# Sh_Input.net
KiCad netlist of a schematic drawn in Altium Designer
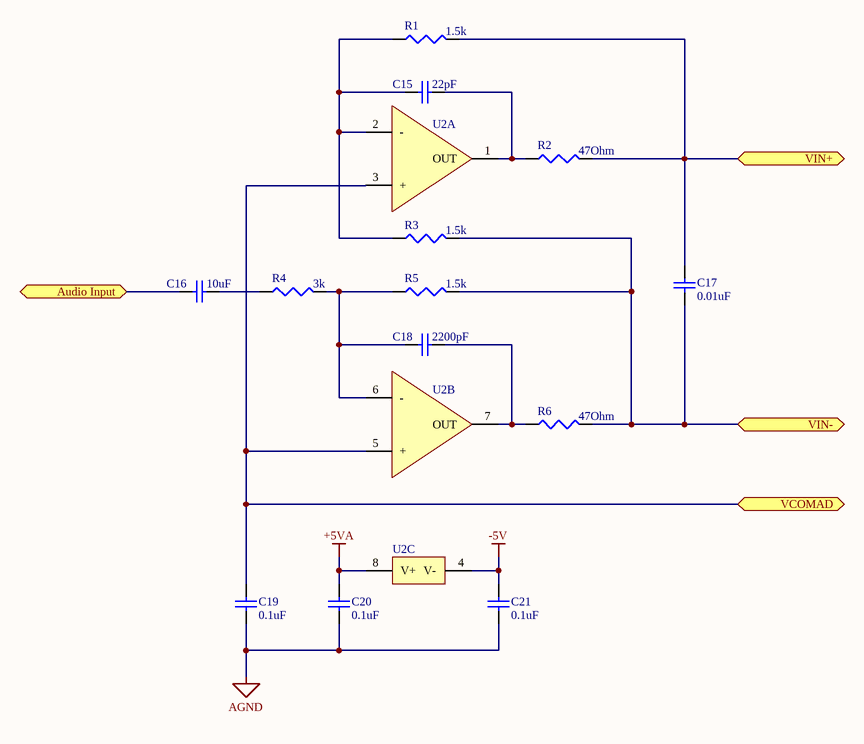
[diagram p0: Sh_Input.SchDoc]

(export (version "E")
  (design (tool "Eeschema 10.0.6"))
  (components
    (comp (ref "C15")
      (value "22pF")
      (footprint "1608[0603]")
      (description "Capacitor (Semiconductor SIM Model)")
      (fields (field (name "Comment") "Cap Semi") (field (name "PUBLISHER") "Altium Limited"))
      (libsource (lib "Miscellaneous Devices") (part "Cap Semi"))
    )
    (comp (ref "C16")
      (value "10uF")
      (footprint "1608[0603]")
      (description "Capacitor (Semiconductor SIM Model)")
      (fields (field (name "Comment") "Cap Semi") (field (name "PUBLISHER") "Altium Limited"))
      (libsource (lib "Miscellaneous Devices") (part "Cap Semi"))
    )
    (comp (ref "C17")
      (value "0.01uF")
      (footprint "1608[0603]")
      (description "Capacitor (Semiconductor SIM Model)")
      (fields (field (name "Comment") "Cap Semi") (field (name "PUBLISHER") "Altium Limited"))
      (libsource (lib "Miscellaneous Devices") (part "Cap Semi"))
    )
    (comp (ref "C18")
      (value "2200pF")
      (footprint "1608[0603]")
      (description "Capacitor (Semiconductor SIM Model)")
      (fields (field (name "Comment") "Cap Semi") (field (name "PUBLISHER") "Altium Limited"))
      (libsource (lib "Miscellaneous Devices") (part "Cap Semi"))
    )
    (comp (ref "C19")
      (value "0.1uF")
      (footprint "1608[0603]")
      (description "Capacitor (Semiconductor SIM Model)")
      (fields (field (name "Comment") "Cap Semi") (field (name "PUBLISHER") "Altium Limited"))
      (libsource (lib "Miscellaneous Devices") (part "Cap Semi"))
    )
    (comp (ref "C20")
      (value "0.1uF")
      (footprint "1608[0603]")
      (description "Capacitor (Semiconductor SIM Model)")
      (fields (field (name "Comment") "Cap Semi") (field (name "PUBLISHER") "Altium Limited"))
      (libsource (lib "Miscellaneous Devices") (part "Cap Semi"))
    )
    (comp (ref "C21")
      (value "0.1uF")
      (footprint "1608[0603]")
      (description "Capacitor (Semiconductor SIM Model)")
      (fields (field (name "Comment") "Cap Semi") (field (name "PUBLISHER") "Altium Limited"))
      (libsource (lib "Miscellaneous Devices") (part "Cap Semi"))
    )
    (comp (ref "R1")
      (value "1.5k")
      (footprint "J1-0603")
      (description "Resistor")
      (fields (field (name "Comment") "Res3") (field (name "PUBLISHER") "Altium Limited"))
      (libsource (lib "Miscellaneous Devices") (part "Res3"))
    )
    (comp (ref "R2")
      (value "47Ohm")
      (footprint "J1-0603")
      (description "Resistor")
      (fields (field (name "Comment") "Res3") (field (name "PUBLISHER") "Altium Limited"))
      (libsource (lib "Miscellaneous Devices") (part "Res3"))
    )
    (comp (ref "R3")
      (value "1.5k")
      (footprint "J1-0603")
      (description "Resistor")
      (fields (field (name "Comment") "Res3") (field (name "PUBLISHER") "Altium Limited"))
      (libsource (lib "Miscellaneous Devices") (part "Res3"))
    )
    (comp (ref "R4")
      (value "3k")
      (footprint "J1-0603")
      (description "Resistor")
      (fields (field (name "Comment") "Res3") (field (name "PUBLISHER") "Altium Limited"))
      (libsource (lib "Miscellaneous Devices") (part "Res3"))
    )
    (comp (ref "R5")
      (value "1.5k")
      (footprint "J1-0603")
      (description "Resistor")
      (fields (field (name "Comment") "Res3") (field (name "PUBLISHER") "Altium Limited"))
      (libsource (lib "Miscellaneous Devices") (part "Res3"))
    )
    (comp (ref "R6")
      (value "47Ohm")
      (footprint "J1-0603")
      (description "Resistor")
      (fields (field (name "Comment") "Res3") (field (name "PUBLISHER") "Altium Limited"))
      (libsource (lib "Miscellaneous Devices") (part "Res3"))
    )
    (comp (ref "U2")
      (value "NE5532A")
      (footprint "SOIC127P600-8AL")
      (description "Amplificateur Opérationnel")
      (libsource (lib "Bonjour") (part "Ampli_op"))
    )
  )
  (nets
    (net (code "1") (name "+5VA") (class "Default")
      (node (ref "C20") (pin "1") (pinfunction "1_1") (pintype "passive"))
      (node (ref "U2") (pin "8") (pinfunction "V+_8") (pintype "passive"))
    )
    (net (code "2") (name "-5V") (class "Default")
      (node (ref "C21") (pin "1") (pinfunction "1_1") (pintype "passive"))
      (node (ref "U2") (pin "4") (pinfunction "V-_4") (pintype "passive"))
    )
    (net (code "3") (name "/Audio Input") (class "Default")
      (node (ref "C16") (pin "2") (pinfunction "2_2") (pintype "passive"))
    )
    (net (code "4") (name "/VCOMAD") (class "Default")
      (node (ref "C19") (pin "1") (pinfunction "1_1") (pintype "passive"))
      (node (ref "U2") (pin "3") (pinfunction "+_3") (pintype "passive"))
      (node (ref "U2") (pin "5") (pinfunction "+_5") (pintype "passive"))
    )
    (net (code "5") (name "/VIN+") (class "Default")
      (node (ref "C17") (pin "1") (pinfunction "1_1") (pintype "passive"))
      (node (ref "R1") (pin "2") (pinfunction "2_2") (pintype "passive"))
      (node (ref "R2") (pin "2") (pinfunction "2_2") (pintype "passive"))
    )
    (net (code "6") (name "/VIN-") (class "Default")
      (node (ref "C17") (pin "2") (pinfunction "2_2") (pintype "passive"))
      (node (ref "R3") (pin "2") (pinfunction "2_2") (pintype "passive"))
      (node (ref "R5") (pin "2") (pinfunction "2_2") (pintype "passive"))
      (node (ref "R6") (pin "2") (pinfunction "2_2") (pintype "passive"))
    )
    (net (code "7") (name "AGND") (class "Default")
      (node (ref "C19") (pin "2") (pinfunction "2_2") (pintype "passive"))
      (node (ref "C20") (pin "2") (pinfunction "2_2") (pintype "passive"))
      (node (ref "C21") (pin "2") (pinfunction "2_2") (pintype "passive"))
    )
    (net (code "8") (name "Net-(C16-Pad1)") (class "Default")
      (node (ref "C16") (pin "1") (pinfunction "1_1") (pintype "passive"))
      (node (ref "R4") (pin "1") (pinfunction "1_1") (pintype "passive"))
    )
    (net (code "9") (name "Net-(U2A--)") (class "Default")
      (node (ref "C15") (pin "2") (pinfunction "2_2") (pintype "passive"))
      (node (ref "R1") (pin "1") (pinfunction "1_1") (pintype "passive"))
      (node (ref "R3") (pin "1") (pinfunction "1_1") (pintype "passive"))
      (node (ref "U2") (pin "2") (pinfunction "-_2") (pintype "passive"))
    )
    (net (code "10") (name "Net-(U2A-OUT)") (class "Default")
      (node (ref "C15") (pin "1") (pinfunction "1_1") (pintype "passive"))
      (node (ref "R2") (pin "1") (pinfunction "1_1") (pintype "passive"))
      (node (ref "U2") (pin "1") (pinfunction "OUT_1") (pintype "passive"))
    )
    (net (code "11") (name "Net-(U2B--)") (class "Default")
      (node (ref "C18") (pin "2") (pinfunction "2_2") (pintype "passive"))
      (node (ref "R4") (pin "2") (pinfunction "2_2") (pintype "passive"))
      (node (ref "R5") (pin "1") (pinfunction "1_1") (pintype "passive"))
      (node (ref "U2") (pin "6") (pinfunction "-_6") (pintype "passive"))
    )
    (net (code "12") (name "Net-(U2B-OUT)") (class "Default")
      (node (ref "C18") (pin "1") (pinfunction "1_1") (pintype "passive"))
      (node (ref "R6") (pin "1") (pinfunction "1_1") (pintype "passive"))
      (node (ref "U2") (pin "7") (pinfunction "OUT_7") (pintype "passive"))
    )
  )
)
